# AMC_Connector.net
KiCad netlist of a schematic drawn in Altium Designer
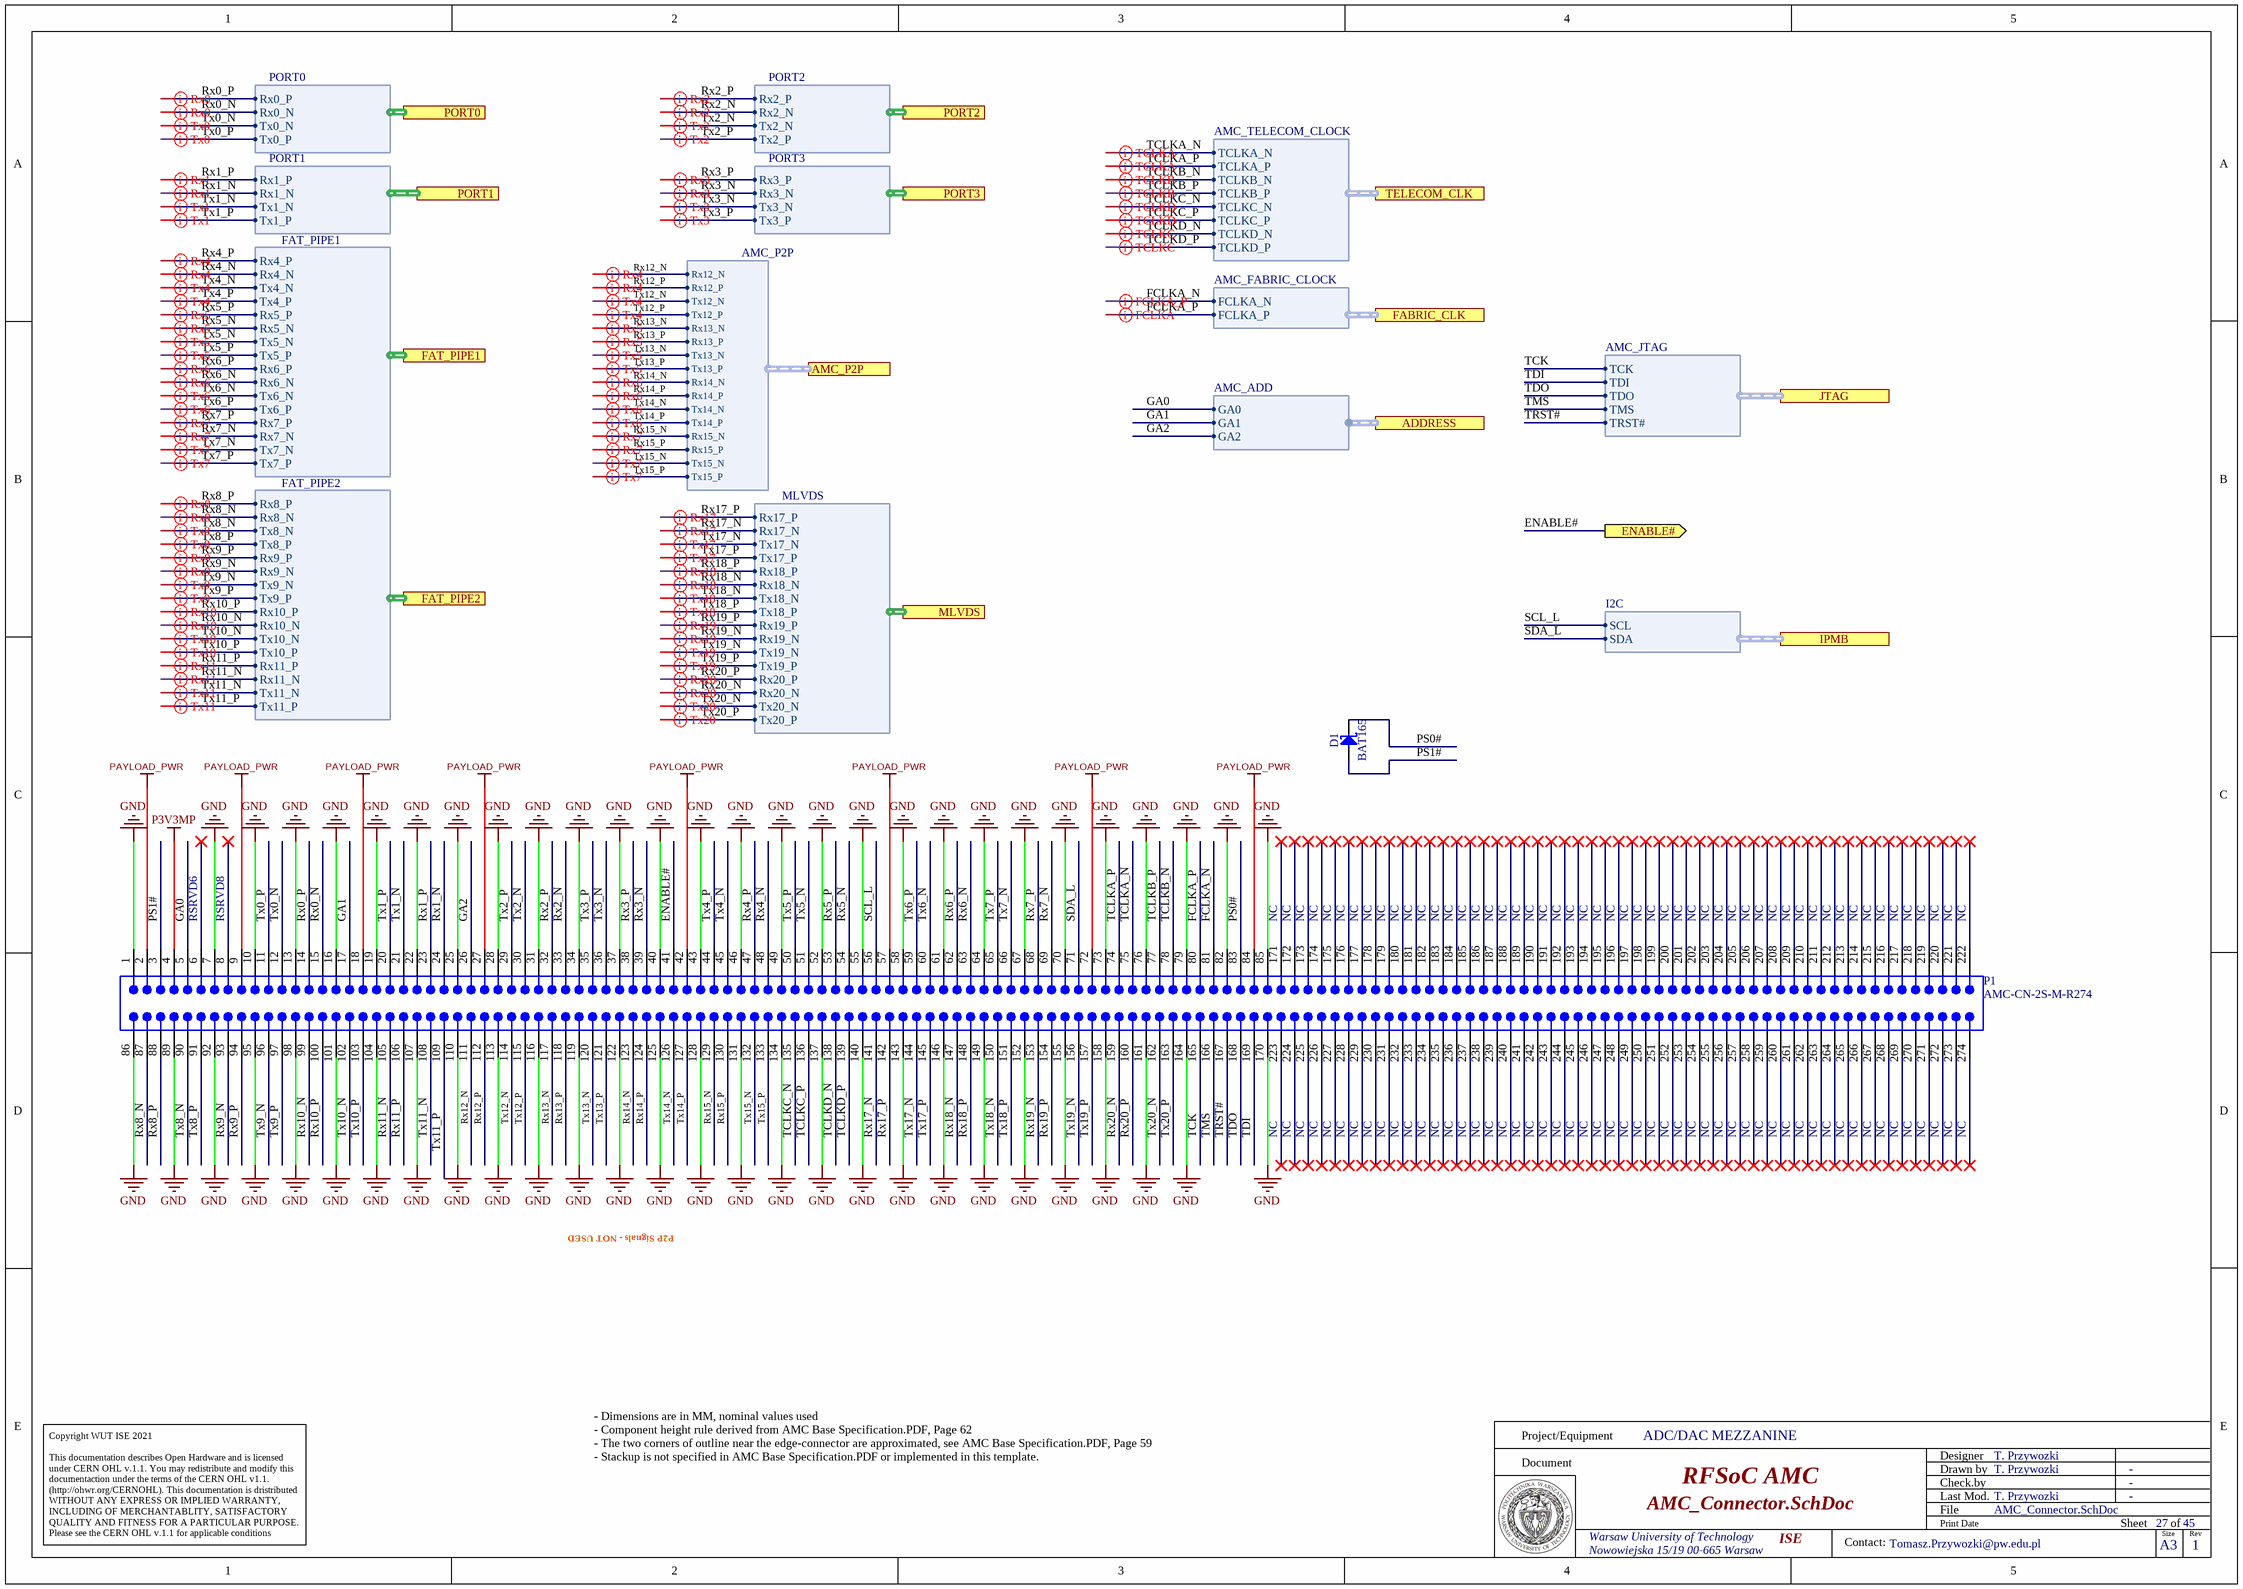
[diagram p0: AMC_Connector.SchDoc]

(export (version "E")
  (design (tool "Eeschema 10.0.6"))
  (components
    (comp (ref "D1")
      (value "BAT165")
      (footprint "SOD2512X110N")
      (description "Schottky Diode")
      (fields
        (field (name "MANUFACTURER") "INFINEON")
        (field (name "VOLTAGE") "40V")
        (field (name "AUTHOR") "CERN DEM JLC")
      )
      (libsource (lib "ICs And Semiconductors") (part "Diode Schottky"))
    )
    (comp (ref "P1")
      (value "AMC-CN-2S-M-R274")
      (footprint "AMC-GF-2D-750-O274")
      (description "Golden finger, AMC, Dual, Opposite, Pitch 0.75mm, 170-Position")
      (fields (field (name "PUBLISHER") "Altium"))
      (libsource (lib "Altium Shanghai") (part "CMP-0001-00058-2"))
    )
  )
  (nets
    (net (code "14") (name "/ENABLE#") (class "Default")
      (node (ref "P1") (pin "41") (pinfunction "41_41") (pintype "passive"))
    )
    (net (code "15") (name "/FCLKA_N") (class "Default")
      (node (ref "P1") (pin "81") (pinfunction "81_81") (pintype "passive"))
    )
    (net (code "16") (name "/FCLKA_P") (class "Default")
      (node (ref "P1") (pin "80") (pinfunction "80_80") (pintype "passive"))
    )
    (net (code "17") (name "/GA0") (class "Default")
      (node (ref "P1") (pin "5") (pinfunction "5_5") (pintype "passive"))
    )
    (net (code "18") (name "/GA1") (class "Default")
      (node (ref "P1") (pin "17") (pinfunction "17_17") (pintype "passive"))
    )
    (net (code "19") (name "/GA2") (class "Default")
      (node (ref "P1") (pin "26") (pinfunction "26_26") (pintype "passive"))
    )
    (net (code "20") (name "/PS0#") (class "Default")
      (node (ref "D1") (pin "1") (pinfunction "C_1") (pintype "passive"))
      (node (ref "P1") (pin "83") (pinfunction "83_83") (pintype "passive"))
    )
    (net (code "21") (name "/PS1#") (class "Default")
      (node (ref "D1") (pin "2") (pinfunction "A_2") (pintype "passive"))
      (node (ref "P1") (pin "3") (pinfunction "3_3") (pintype "passive"))
    )
    (net (code "22") (name "/Rx0_N") (class "Default")
      (node (ref "P1") (pin "15") (pinfunction "15_15") (pintype "passive"))
    )
    (net (code "23") (name "/Rx0_P") (class "Default")
      (node (ref "P1") (pin "14") (pinfunction "14_14") (pintype "passive"))
    )
    (net (code "24") (name "/Rx1_N") (class "Default")
      (node (ref "P1") (pin "24") (pinfunction "24_24") (pintype "passive"))
    )
    (net (code "25") (name "/Rx1_P") (class "Default")
      (node (ref "P1") (pin "23") (pinfunction "23_23") (pintype "passive"))
    )
    (net (code "26") (name "/Rx2_N") (class "Default")
      (node (ref "P1") (pin "33") (pinfunction "33_33") (pintype "passive"))
    )
    (net (code "27") (name "/Rx2_P") (class "Default")
      (node (ref "P1") (pin "32") (pinfunction "32_32") (pintype "passive"))
    )
    (net (code "28") (name "/Rx3_N") (class "Default")
      (node (ref "P1") (pin "39") (pinfunction "39_39") (pintype "passive"))
    )
    (net (code "29") (name "/Rx3_P") (class "Default")
      (node (ref "P1") (pin "38") (pinfunction "38_38") (pintype "passive"))
    )
    (net (code "30") (name "/Rx4_N") (class "Default")
      (node (ref "P1") (pin "48") (pinfunction "48_48") (pintype "passive"))
    )
    (net (code "31") (name "/Rx4_P") (class "Default")
      (node (ref "P1") (pin "47") (pinfunction "47_47") (pintype "passive"))
    )
    (net (code "32") (name "/Rx5_N") (class "Default")
      (node (ref "P1") (pin "54") (pinfunction "54_54") (pintype "passive"))
    )
    (net (code "33") (name "/Rx5_P") (class "Default")
      (node (ref "P1") (pin "53") (pinfunction "53_53") (pintype "passive"))
    )
    (net (code "34") (name "/Rx6_N") (class "Default")
      (node (ref "P1") (pin "63") (pinfunction "63_63") (pintype "passive"))
    )
    (net (code "35") (name "/Rx6_P") (class "Default")
      (node (ref "P1") (pin "62") (pinfunction "62_62") (pintype "passive"))
    )
    (net (code "36") (name "/Rx7_N") (class "Default")
      (node (ref "P1") (pin "69") (pinfunction "69_69") (pintype "passive"))
    )
    (net (code "37") (name "/Rx7_P") (class "Default")
      (node (ref "P1") (pin "68") (pinfunction "68_68") (pintype "passive"))
    )
    (net (code "38") (name "/Rx8_N") (class "Default")
      (node (ref "P1") (pin "87") (pinfunction "87_87") (pintype "passive"))
    )
    (net (code "39") (name "/Rx8_P") (class "Default")
      (node (ref "P1") (pin "88") (pinfunction "88_88") (pintype "passive"))
    )
    (net (code "40") (name "/Rx9_N") (class "Default")
      (node (ref "P1") (pin "93") (pinfunction "93_93") (pintype "passive"))
    )
    (net (code "41") (name "/Rx9_P") (class "Default")
      (node (ref "P1") (pin "94") (pinfunction "94_94") (pintype "passive"))
    )
    (net (code "42") (name "/Rx10_N") (class "Default")
      (node (ref "P1") (pin "99") (pinfunction "99_99") (pintype "passive"))
    )
    (net (code "43") (name "/Rx10_P") (class "Default")
      (node (ref "P1") (pin "100") (pinfunction "100_100") (pintype "passive"))
    )
    (net (code "44") (name "/Rx11_N") (class "Default")
      (node (ref "P1") (pin "105") (pinfunction "105_105") (pintype "passive"))
    )
    (net (code "45") (name "/Rx11_P") (class "Default")
      (node (ref "P1") (pin "106") (pinfunction "106_106") (pintype "passive"))
    )
    (net (code "46") (name "/Rx12_N") (class "Default")
      (node (ref "P1") (pin "111") (pinfunction "111_111") (pintype "passive"))
    )
    (net (code "47") (name "/Rx12_P") (class "Default")
      (node (ref "P1") (pin "112") (pinfunction "112_112") (pintype "passive"))
    )
    (net (code "48") (name "/Rx13_N") (class "Default")
      (node (ref "P1") (pin "117") (pinfunction "117_117") (pintype "passive"))
    )
    (net (code "49") (name "/Rx13_P") (class "Default")
      (node (ref "P1") (pin "118") (pinfunction "118_118") (pintype "passive"))
    )
    (net (code "50") (name "/Rx14_N") (class "Default")
      (node (ref "P1") (pin "123") (pinfunction "123_123") (pintype "passive"))
    )
    (net (code "51") (name "/Rx14_P") (class "Default")
      (node (ref "P1") (pin "124") (pinfunction "124_124") (pintype "passive"))
    )
    (net (code "52") (name "/Rx15_N") (class "Default")
      (node (ref "P1") (pin "129") (pinfunction "129_129") (pintype "passive"))
    )
    (net (code "53") (name "/Rx15_P") (class "Default")
      (node (ref "P1") (pin "130") (pinfunction "130_130") (pintype "passive"))
    )
    (net (code "54") (name "/Rx17_N") (class "Default")
      (node (ref "P1") (pin "141") (pinfunction "141_141") (pintype "passive"))
    )
    (net (code "55") (name "/Rx17_P") (class "Default")
      (node (ref "P1") (pin "142") (pinfunction "142_142") (pintype "passive"))
    )
    (net (code "56") (name "/Rx18_N") (class "Default")
      (node (ref "P1") (pin "147") (pinfunction "147_147") (pintype "passive"))
    )
    (net (code "57") (name "/Rx18_P") (class "Default")
      (node (ref "P1") (pin "148") (pinfunction "148_148") (pintype "passive"))
    )
    (net (code "58") (name "/Rx19_N") (class "Default")
      (node (ref "P1") (pin "153") (pinfunction "153_153") (pintype "passive"))
    )
    (net (code "59") (name "/Rx19_P") (class "Default")
      (node (ref "P1") (pin "154") (pinfunction "154_154") (pintype "passive"))
    )
    (net (code "60") (name "/Rx20_N") (class "Default")
      (node (ref "P1") (pin "159") (pinfunction "159_159") (pintype "passive"))
    )
    (net (code "61") (name "/Rx20_P") (class "Default")
      (node (ref "P1") (pin "160") (pinfunction "160_160") (pintype "passive"))
    )
    (net (code "62") (name "/SCL_L") (class "Default")
      (node (ref "P1") (pin "56") (pinfunction "56_56") (pintype "passive"))
    )
    (net (code "63") (name "/SDA_L") (class "Default")
      (node (ref "P1") (pin "71") (pinfunction "71_71") (pintype "passive"))
    )
    (net (code "64") (name "/TCK") (class "Default")
      (node (ref "P1") (pin "165") (pinfunction "165_165") (pintype "passive"))
    )
    (net (code "65") (name "/TCLKA_N") (class "Default")
      (node (ref "P1") (pin "75") (pinfunction "75_75") (pintype "passive"))
    )
    (net (code "66") (name "/TCLKA_P") (class "Default")
      (node (ref "P1") (pin "74") (pinfunction "74_74") (pintype "passive"))
    )
    (net (code "67") (name "/TCLKB_N") (class "Default")
      (node (ref "P1") (pin "78") (pinfunction "78_78") (pintype "passive"))
    )
    (net (code "68") (name "/TCLKB_P") (class "Default")
      (node (ref "P1") (pin "77") (pinfunction "77_77") (pintype "passive"))
    )
    (net (code "69") (name "/TCLKC_N") (class "Default")
      (node (ref "P1") (pin "135") (pinfunction "135_135") (pintype "passive"))
    )
    (net (code "70") (name "/TCLKC_P") (class "Default")
      (node (ref "P1") (pin "136") (pinfunction "136_136") (pintype "passive"))
    )
    (net (code "71") (name "/TCLKD_N") (class "Default")
      (node (ref "P1") (pin "138") (pinfunction "138_138") (pintype "passive"))
    )
    (net (code "72") (name "/TCLKD_P") (class "Default")
      (node (ref "P1") (pin "139") (pinfunction "139_139") (pintype "passive"))
    )
    (net (code "73") (name "/TDI") (class "Default")
      (node (ref "P1") (pin "169") (pinfunction "169_169") (pintype "passive"))
    )
    (net (code "74") (name "/TDO") (class "Default")
      (node (ref "P1") (pin "168") (pinfunction "168_168") (pintype "passive"))
    )
    (net (code "75") (name "/TMS") (class "Default")
      (node (ref "P1") (pin "166") (pinfunction "166_166") (pintype "passive"))
    )
    (net (code "76") (name "/TRST#") (class "Default")
      (node (ref "P1") (pin "167") (pinfunction "167_167") (pintype "passive"))
    )
    (net (code "77") (name "/Tx0_N") (class "Default")
      (node (ref "P1") (pin "12") (pinfunction "12_12") (pintype "passive"))
    )
    (net (code "78") (name "/Tx0_P") (class "Default")
      (node (ref "P1") (pin "11") (pinfunction "11_11") (pintype "passive"))
    )
    (net (code "79") (name "/Tx1_N") (class "Default")
      (node (ref "P1") (pin "21") (pinfunction "21_21") (pintype "passive"))
    )
    (net (code "80") (name "/Tx1_P") (class "Default")
      (node (ref "P1") (pin "20") (pinfunction "20_20") (pintype "passive"))
    )
    (net (code "81") (name "/Tx2_N") (class "Default")
      (node (ref "P1") (pin "30") (pinfunction "30_30") (pintype "passive"))
    )
    (net (code "82") (name "/Tx2_P") (class "Default")
      (node (ref "P1") (pin "29") (pinfunction "29_29") (pintype "passive"))
    )
    (net (code "83") (name "/Tx3_N") (class "Default")
      (node (ref "P1") (pin "36") (pinfunction "36_36") (pintype "passive"))
    )
    (net (code "84") (name "/Tx3_P") (class "Default")
      (node (ref "P1") (pin "35") (pinfunction "35_35") (pintype "passive"))
    )
    (net (code "85") (name "/Tx4_N") (class "Default")
      (node (ref "P1") (pin "45") (pinfunction "45_45") (pintype "passive"))
    )
    (net (code "86") (name "/Tx4_P") (class "Default")
      (node (ref "P1") (pin "44") (pinfunction "44_44") (pintype "passive"))
    )
    (net (code "87") (name "/Tx5_N") (class "Default")
      (node (ref "P1") (pin "51") (pinfunction "51_51") (pintype "passive"))
    )
    (net (code "88") (name "/Tx5_P") (class "Default")
      (node (ref "P1") (pin "50") (pinfunction "50_50") (pintype "passive"))
    )
    (net (code "89") (name "/Tx6_N") (class "Default")
      (node (ref "P1") (pin "60") (pinfunction "60_60") (pintype "passive"))
    )
    (net (code "90") (name "/Tx6_P") (class "Default")
      (node (ref "P1") (pin "59") (pinfunction "59_59") (pintype "passive"))
    )
    (net (code "91") (name "/Tx7_N") (class "Default")
      (node (ref "P1") (pin "66") (pinfunction "66_66") (pintype "passive"))
    )
    (net (code "92") (name "/Tx7_P") (class "Default")
      (node (ref "P1") (pin "65") (pinfunction "65_65") (pintype "passive"))
    )
    (net (code "93") (name "/Tx8_N") (class "Default")
      (node (ref "P1") (pin "90") (pinfunction "90_90") (pintype "passive"))
    )
    (net (code "94") (name "/Tx8_P") (class "Default")
      (node (ref "P1") (pin "91") (pinfunction "91_91") (pintype "passive"))
    )
    (net (code "95") (name "/Tx9_N") (class "Default")
      (node (ref "P1") (pin "96") (pinfunction "96_96") (pintype "passive"))
    )
    (net (code "96") (name "/Tx9_P") (class "Default")
      (node (ref "P1") (pin "97") (pinfunction "97_97") (pintype "passive"))
    )
    (net (code "97") (name "/Tx10_N") (class "Default")
      (node (ref "P1") (pin "102") (pinfunction "102_102") (pintype "passive"))
    )
    (net (code "98") (name "/Tx10_P") (class "Default")
      (node (ref "P1") (pin "103") (pinfunction "103_103") (pintype "passive"))
    )
    (net (code "99") (name "/Tx11_N") (class "Default")
      (node (ref "P1") (pin "108") (pinfunction "108_108") (pintype "passive"))
    )
    (net (code "100") (name "/Tx11_P") (class "Default")
      (node (ref "P1") (pin "109") (pinfunction "109_109") (pintype "passive"))
    )
    (net (code "101") (name "/Tx12_N") (class "Default")
      (node (ref "P1") (pin "114") (pinfunction "114_114") (pintype "passive"))
    )
    (net (code "102") (name "/Tx12_P") (class "Default")
      (node (ref "P1") (pin "115") (pinfunction "115_115") (pintype "passive"))
    )
    (net (code "103") (name "/Tx13_N") (class "Default")
      (node (ref "P1") (pin "120") (pinfunction "120_120") (pintype "passive"))
    )
    (net (code "104") (name "/Tx13_P") (class "Default")
      (node (ref "P1") (pin "121") (pinfunction "121_121") (pintype "passive"))
    )
    (net (code "105") (name "/Tx14_N") (class "Default")
      (node (ref "P1") (pin "126") (pinfunction "126_126") (pintype "passive"))
    )
    (net (code "106") (name "/Tx14_P") (class "Default")
      (node (ref "P1") (pin "127") (pinfunction "127_127") (pintype "passive"))
    )
    (net (code "107") (name "/Tx15_N") (class "Default")
      (node (ref "P1") (pin "132") (pinfunction "132_132") (pintype "passive"))
    )
    (net (code "108") (name "/Tx15_P") (class "Default")
      (node (ref "P1") (pin "133") (pinfunction "133_133") (pintype "passive"))
    )
    (net (code "109") (name "/Tx17_N") (class "Default")
      (node (ref "P1") (pin "144") (pinfunction "144_144") (pintype "passive"))
    )
    (net (code "110") (name "/Tx17_P") (class "Default")
      (node (ref "P1") (pin "145") (pinfunction "145_145") (pintype "passive"))
    )
    (net (code "111") (name "/Tx18_N") (class "Default")
      (node (ref "P1") (pin "150") (pinfunction "150_150") (pintype "passive"))
    )
    (net (code "112") (name "/Tx18_P") (class "Default")
      (node (ref "P1") (pin "151") (pinfunction "151_151") (pintype "passive"))
    )
    (net (code "113") (name "/Tx19_N") (class "Default")
      (node (ref "P1") (pin "156") (pinfunction "156_156") (pintype "passive"))
    )
    (net (code "114") (name "/Tx19_P") (class "Default")
      (node (ref "P1") (pin "157") (pinfunction "157_157") (pintype "passive"))
    )
    (net (code "115") (name "/Tx20_N") (class "Default")
      (node (ref "P1") (pin "162") (pinfunction "162_162") (pintype "passive"))
    )
    (net (code "116") (name "/Tx20_P") (class "Default")
      (node (ref "P1") (pin "163") (pinfunction "163_163") (pintype "passive"))
    )
    (net (code "130") (name "GND") (class "Default")
      (node (ref "P1") (pin "1") (pinfunction "1_1") (pintype "passive"))
      (node (ref "P1") (pin "10") (pinfunction "10_10") (pintype "passive"))
      (node (ref "P1") (pin "101") (pinfunction "101_101") (pintype "passive"))
      (node (ref "P1") (pin "104") (pinfunction "104_104") (pintype "passive"))
      (node (ref "P1") (pin "107") (pinfunction "107_107") (pintype "passive"))
      (node (ref "P1") (pin "110") (pinfunction "110_110") (pintype "passive"))
      (node (ref "P1") (pin "113") (pinfunction "113_113") (pintype "passive"))
      (node (ref "P1") (pin "116") (pinfunction "116_116") (pintype "passive"))
      (node (ref "P1") (pin "119") (pinfunction "119_119") (pintype "passive"))
      (node (ref "P1") (pin "122") (pinfunction "122_122") (pintype "passive"))
      (node (ref "P1") (pin "125") (pinfunction "125_125") (pintype "passive"))
      (node (ref "P1") (pin "128") (pinfunction "128_128") (pintype "passive"))
      (node (ref "P1") (pin "13") (pinfunction "13_13") (pintype "passive"))
      (node (ref "P1") (pin "131") (pinfunction "131_131") (pintype "passive"))
      (node (ref "P1") (pin "134") (pinfunction "134_134") (pintype "passive"))
      (node (ref "P1") (pin "137") (pinfunction "137_137") (pintype "passive"))
      (node (ref "P1") (pin "140") (pinfunction "140_140") (pintype "passive"))
      (node (ref "P1") (pin "143") (pinfunction "143_143") (pintype "passive"))
      (node (ref "P1") (pin "146") (pinfunction "146_146") (pintype "passive"))
      (node (ref "P1") (pin "149") (pinfunction "149_149") (pintype "passive"))
      (node (ref "P1") (pin "152") (pinfunction "152_152") (pintype "passive"))
      (node (ref "P1") (pin "155") (pinfunction "155_155") (pintype "passive"))
      (node (ref "P1") (pin "158") (pinfunction "158_158") (pintype "passive"))
      (node (ref "P1") (pin "16") (pinfunction "16_16") (pintype "passive"))
      (node (ref "P1") (pin "161") (pinfunction "161_161") (pintype "passive"))
      (node (ref "P1") (pin "164") (pinfunction "164_164") (pintype "passive"))
      (node (ref "P1") (pin "170") (pinfunction "170_170") (pintype "passive"))
      (node (ref "P1") (pin "19") (pinfunction "19_19") (pintype "passive"))
      (node (ref "P1") (pin "22") (pinfunction "22_22") (pintype "passive"))
      (node (ref "P1") (pin "25") (pinfunction "25_25") (pintype "passive"))
      (node (ref "P1") (pin "28") (pinfunction "28_28") (pintype "passive"))
      (node (ref "P1") (pin "31") (pinfunction "31_31") (pintype "passive"))
      (node (ref "P1") (pin "34") (pinfunction "34_34") (pintype "passive"))
      (node (ref "P1") (pin "37") (pinfunction "37_37") (pintype "passive"))
      (node (ref "P1") (pin "40") (pinfunction "40_40") (pintype "passive"))
      (node (ref "P1") (pin "43") (pinfunction "43_43") (pintype "passive"))
      (node (ref "P1") (pin "46") (pinfunction "46_46") (pintype "passive"))
      (node (ref "P1") (pin "49") (pinfunction "49_49") (pintype "passive"))
      (node (ref "P1") (pin "52") (pinfunction "52_52") (pintype "passive"))
      (node (ref "P1") (pin "55") (pinfunction "55_55") (pintype "passive"))
      (node (ref "P1") (pin "58") (pinfunction "58_58") (pintype "passive"))
      (node (ref "P1") (pin "61") (pinfunction "61_61") (pintype "passive"))
      (node (ref "P1") (pin "64") (pinfunction "64_64") (pintype "passive"))
      (node (ref "P1") (pin "67") (pinfunction "67_67") (pintype "passive"))
      (node (ref "P1") (pin "7") (pinfunction "7_7") (pintype "passive"))
      (node (ref "P1") (pin "70") (pinfunction "70_70") (pintype "passive"))
      (node (ref "P1") (pin "73") (pinfunction "73_73") (pintype "passive"))
      (node (ref "P1") (pin "76") (pinfunction "76_76") (pintype "passive"))
      (node (ref "P1") (pin "79") (pinfunction "79_79") (pintype "passive"))
      (node (ref "P1") (pin "82") (pinfunction "82_82") (pintype "passive"))
      (node (ref "P1") (pin "85") (pinfunction "85_85") (pintype "passive"))
      (node (ref "P1") (pin "86") (pinfunction "86_86") (pintype "passive"))
      (node (ref "P1") (pin "89") (pinfunction "89_89") (pintype "passive"))
      (node (ref "P1") (pin "92") (pinfunction "92_92") (pintype "passive"))
      (node (ref "P1") (pin "95") (pinfunction "95_95") (pintype "passive"))
      (node (ref "P1") (pin "98") (pinfunction "98_98") (pintype "passive"))
    )
    (net (code "131") (name "P3V3MP") (class "Default")
      (node (ref "P1") (pin "4") (pinfunction "4_4") (pintype "passive"))
    )
    (net (code "132") (name "PAYLOAD_PWR") (class "Default")
      (node (ref "P1") (pin "18") (pinfunction "18_18") (pintype "passive"))
      (node (ref "P1") (pin "2") (pinfunction "2_2") (pintype "passive"))
      (node (ref "P1") (pin "27") (pinfunction "27_27") (pintype "passive"))
      (node (ref "P1") (pin "42") (pinfunction "42_42") (pintype "passive"))
      (node (ref "P1") (pin "57") (pinfunction "57_57") (pintype "passive"))
      (node (ref "P1") (pin "72") (pinfunction "72_72") (pintype "passive"))
      (node (ref "P1") (pin "84") (pinfunction "84_84") (pintype "passive"))
      (node (ref "P1") (pin "9") (pinfunction "9_9") (pintype "passive"))
    )
    (net (code "133") (name "unconnected-(P1-Pad6)") (class "Default")
      (node (ref "P1") (pin "6") (pinfunction "6_6") (pintype "passive+no_connect"))
    )
    (net (code "134") (name "unconnected-(P1-Pad8)") (class "Default")
      (node (ref "P1") (pin "8") (pinfunction "8_8") (pintype "passive+no_connect"))
    )
    (net (code "135") (name "unconnected-(P1-Pad171)") (class "Default")
      (node (ref "P1") (pin "171") (pinfunction "171_171") (pintype "passive+no_connect"))
    )
    (net (code "136") (name "unconnected-(P1-Pad172)") (class "Default")
      (node (ref "P1") (pin "172") (pinfunction "172_172") (pintype "passive+no_connect"))
    )
    (net (code "137") (name "unconnected-(P1-Pad173)") (class "Default")
      (node (ref "P1") (pin "173") (pinfunction "173_173") (pintype "passive+no_connect"))
    )
    (net (code "138") (name "unconnected-(P1-Pad174)") (class "Default")
      (node (ref "P1") (pin "174") (pinfunction "174_174") (pintype "passive+no_connect"))
    )
    (net (code "139") (name "unconnected-(P1-Pad175)") (class "Default")
      (node (ref "P1") (pin "175") (pinfunction "175_175") (pintype "passive+no_connect"))
    )
    (net (code "140") (name "unconnected-(P1-Pad176)") (class "Default")
      (node (ref "P1") (pin "176") (pinfunction "176_176") (pintype "passive+no_connect"))
    )
    (net (code "141") (name "unconnected-(P1-Pad177)") (class "Default")
      (node (ref "P1") (pin "177") (pinfunction "177_177") (pintype "passive+no_connect"))
    )
    (net (code "142") (name "unconnected-(P1-Pad178)") (class "Default")
      (node (ref "P1") (pin "178") (pinfunction "178_178") (pintype "passive+no_connect"))
    )
    (net (code "143") (name "unconnected-(P1-Pad179)") (class "Default")
      (node (ref "P1") (pin "179") (pinfunction "179_179") (pintype "passive+no_connect"))
    )
    (net (code "144") (name "unconnected-(P1-Pad180)") (class "Default")
      (node (ref "P1") (pin "180") (pinfunction "180_180") (pintype "passive+no_connect"))
    )
    (net (code "145") (name "unconnected-(P1-Pad181)") (class "Default")
      (node (ref "P1") (pin "181") (pinfunction "181_181") (pintype "passive+no_connect"))
    )
    (net (code "146") (name "unconnected-(P1-Pad182)") (class "Default")
      (node (ref "P1") (pin "182") (pinfunction "182_182") (pintype "passive+no_connect"))
    )
    (net (code "147") (name "unconnected-(P1-Pad183)") (class "Default")
      (node (ref "P1") (pin "183") (pinfunction "183_183") (pintype "passive+no_connect"))
    )
    (net (code "148") (name "unconnected-(P1-Pad184)") (class "Default")
      (node (ref "P1") (pin "184") (pinfunction "184_184") (pintype "passive+no_connect"))
    )
    (net (code "149") (name "unconnected-(P1-Pad185)") (class "Default")
      (node (ref "P1") (pin "185") (pinfunction "185_185") (pintype "passive+no_connect"))
    )
    (net (code "150") (name "unconnected-(P1-Pad186)") (class "Default")
      (node (ref "P1") (pin "186") (pinfunction "186_186") (pintype "passive+no_connect"))
    )
    (net (code "151") (name "unconnected-(P1-Pad187)") (class "Default")
      (node (ref "P1") (pin "187") (pinfunction "187_187") (pintype "passive+no_connect"))
    )
    (net (code "152") (name "unconnected-(P1-Pad188)") (class "Default")
      (node (ref "P1") (pin "188") (pinfunction "188_188") (pintype "passive+no_connect"))
    )
    (net (code "153") (name "unconnected-(P1-Pad189)") (class "Default")
      (node (ref "P1") (pin "189") (pinfunction "189_189") (pintype "passive+no_connect"))
    )
    (net (code "154") (name "unconnected-(P1-Pad190)") (class "Default")
      (node (ref "P1") (pin "190") (pinfunction "190_190") (pintype "passive+no_connect"))
    )
    (net (code "155") (name "unconnected-(P1-Pad191)") (class "Default")
      (node (ref "P1") (pin "191") (pinfunction "191_191") (pintype "passive+no_connect"))
    )
    (net (code "156") (name "unconnected-(P1-Pad192)") (class "Default")
      (node (ref "P1") (pin "192") (pinfunction "192_192") (pintype "passive+no_connect"))
    )
    (net (code "157") (name "unconnected-(P1-Pad193)") (class "Default")
      (node (ref "P1") (pin "193") (pinfunction "193_193") (pintype "passive+no_connect"))
    )
    (net (code "158") (name "unconnected-(P1-Pad194)") (class "Default")
      (node (ref "P1") (pin "194") (pinfunction "194_194") (pintype "passive+no_connect"))
    )
    (net (code "159") (name "unconnected-(P1-Pad195)") (class "Default")
      (node (ref "P1") (pin "195") (pinfunction "195_195") (pintype "passive+no_connect"))
    )
    (net (code "160") (name "unconnected-(P1-Pad196)") (class "Default")
      (node (ref "P1") (pin "196") (pinfunction "196_196") (pintype "passive+no_connect"))
    )
    (net (code "161") (name "unconnected-(P1-Pad197)") (class "Default")
      (node (ref "P1") (pin "197") (pinfunction "197_197") (pintype "passive+no_connect"))
    )
    (net (code "162") (name "unconnected-(P1-Pad198)") (class "Default")
      (node (ref "P1") (pin "198") (pinfunction "198_198") (pintype "passive+no_connect"))
    )
    (net (code "163") (name "unconnected-(P1-Pad199)") (class "Default")
      (node (ref "P1") (pin "199") (pinfunction "199_199") (pintype "passive+no_connect"))
    )
    (net (code "164") (name "unconnected-(P1-Pad200)") (class "Default")
      (node (ref "P1") (pin "200") (pinfunction "200_200") (pintype "passive+no_connect"))
    )
    (net (code "165") (name "unconnected-(P1-Pad201)") (class "Default")
      (node (ref "P1") (pin "201") (pinfunction "201_201") (pintype "passive+no_connect"))
    )
    (net (code "166") (name "unconnected-(P1-Pad202)") (class "Default")
      (node (ref "P1") (pin "202") (pinfunction "202_202") (pintype "passive+no_connect"))
    )
    (net (code "167") (name "unconnected-(P1-Pad203)") (class "Default")
      (node (ref "P1") (pin "203") (pinfunction "203_203") (pintype "passive+no_connect"))
    )
    (net (code "168") (name "unconnected-(P1-Pad204)") (class "Default")
      (node (ref "P1") (pin "204") (pinfunction "204_204") (pintype "passive+no_connect"))
    )
    (net (code "169") (name "unconnected-(P1-Pad205)") (class "Default")
      (node (ref "P1") (pin "205") (pinfunction "205_205") (pintype "passive+no_connect"))
    )
    (net (code "170") (name "unconnected-(P1-Pad206)") (class "Default")
      (node (ref "P1") (pin "206") (pinfunction "206_206") (pintype "passive+no_connect"))
    )
    (net (code "171") (name "unconnected-(P1-Pad207)") (class "Default")
      (node (ref "P1") (pin "207") (pinfunction "207_207") (pintype "passive+no_connect"))
    )
    (net (code "172") (name "unconnected-(P1-Pad208)") (class "Default")
      (node (ref "P1") (pin "208") (pinfunction "208_208") (pintype "passive+no_connect"))
    )
    (net (code "173") (name "unconnected-(P1-Pad209)") (class "Default")
      (node (ref "P1") (pin "209") (pinfunction "209_209") (pintype "passive+no_connect"))
    )
    (net (code "174") (name "unconnected-(P1-Pad210)") (class "Default")
      (node (ref "P1") (pin "210") (pinfunction "210_210") (pintype "passive+no_connect"))
    )
    (net (code "175") (name "unconnected-(P1-Pad211)") (class "Default")
      (node (ref "P1") (pin "211") (pinfunction "211_211") (pintype "passive+no_connect"))
    )
    (net (code "176") (name "unconnected-(P1-Pad212)") (class "Default")
      (node (ref "P1") (pin "212") (pinfunction "212_212") (pintype "passive+no_connect"))
    )
    (net (code "177") (name "unconnected-(P1-Pad213)") (class "Default")
      (node (ref "P1") (pin "213") (pinfunction "213_213") (pintype "passive+no_connect"))
    )
    (net (code "178") (name "unconnected-(P1-Pad214)") (class "Default")
      (node (ref "P1") (pin "214") (pinfunction "214_214") (pintype "passive+no_connect"))
    )
    (net (code "179") (name "unconnected-(P1-Pad215)") (class "Default")
      (node (ref "P1") (pin "215") (pinfunction "215_215") (pintype "passive+no_connect"))
    )
    (net (code "180") (name "unconnected-(P1-Pad216)") (class "Default")
      (node (ref "P1") (pin "216") (pinfunction "216_216") (pintype "passive+no_connect"))
    )
    (net (code "181") (name "unconnected-(P1-Pad217)") (class "Default")
      (node (ref "P1") (pin "217") (pinfunction "217_217") (pintype "passive+no_connect"))
    )
    (net (code "182") (name "unconnected-(P1-Pad218)") (class "Default")
      (node (ref "P1") (pin "218") (pinfunction "218_218") (pintype "passive+no_connect"))
    )
    (net (code "183") (name "unconnected-(P1-Pad219)") (class "Default")
      (node (ref "P1") (pin "219") (pinfunction "219_219") (pintype "passive+no_connect"))
    )
    (net (code "184") (name "unconnected-(P1-Pad220)") (class "Default")
      (node (ref "P1") (pin "220") (pinfunction "220_220") (pintype "passive+no_connect"))
    )
    (net (code "185") (name "unconnected-(P1-Pad221)") (class "Default")
      (node (ref "P1") (pin "221") (pinfunction "221_221") (pintype "passive+no_connect"))
    )
    (net (code "186") (name "unconnected-(P1-Pad222)") (class "Default")
      (node (ref "P1") (pin "222") (pinfunction "222_222") (pintype "passive+no_connect"))
    )
    (net (code "187") (name "unconnected-(P1-Pad223)") (class "Default")
      (node (ref "P1") (pin "223") (pinfunction "223_223") (pintype "passive+no_connect"))
    )
    (net (code "188") (name "unconnected-(P1-Pad224)") (class "Default")
      (node (ref "P1") (pin "224") (pinfunction "224_224") (pintype "passive+no_connect"))
    )
    (net (code "189") (name "unconnected-(P1-Pad225)") (class "Default")
      (node (ref "P1") (pin "225") (pinfunction "225_225") (pintype "passive+no_connect"))
    )
    (net (code "190") (name "unconnected-(P1-Pad226)") (class "Default")
      (node (ref "P1") (pin "226") (pinfunction "226_226") (pintype "passive+no_connect"))
    )
    (net (code "191") (name "unconnected-(P1-Pad227)") (class "Default")
      (node (ref "P1") (pin "227") (pinfunction "227_227") (pintype "passive+no_connect"))
    )
    (net (code "192") (name "unconnected-(P1-Pad228)") (class "Default")
      (node (ref "P1") (pin "228") (pinfunction "228_228") (pintype "passive+no_connect"))
    )
    (net (code "193") (name "unconnected-(P1-Pad229)") (class "Default")
      (node (ref "P1") (pin "229") (pinfunction "229_229") (pintype "passive+no_connect"))
    )
    (net (code "194") (name "unconnected-(P1-Pad230)") (class "Default")
      (node (ref "P1") (pin "230") (pinfunction "230_230") (pintype "passive+no_connect"))
    )
    (net (code "195") (name "unconnected-(P1-Pad231)") (class "Default")
      (node (ref "P1") (pin "231") (pinfunction "231_231") (pintype "passive+no_connect"))
    )
    (net (code "196") (name "unconnected-(P1-Pad232)") (class "Default")
      (node (ref "P1") (pin "232") (pinfunction "232_232") (pintype "passive+no_connect"))
    )
    (net (code "197") (name "unconnected-(P1-Pad233)") (class "Default")
      (node (ref "P1") (pin "233") (pinfunction "233_233") (pintype "passive+no_connect"))
    )
    (net (code "198") (name "unconnected-(P1-Pad234)") (class "Default")
      (node (ref "P1") (pin "234") (pinfunction "234_234") (pintype "passive+no_connect"))
    )
    (net (code "199") (name "unconnected-(P1-Pad235)") (class "Default")
      (node (ref "P1") (pin "235") (pinfunction "235_235") (pintype "passive+no_connect"))
    )
    (net (code "200") (name "unconnected-(P1-Pad236)") (class "Default")
      (node (ref "P1") (pin "236") (pinfunction "236_236") (pintype "passive+no_connect"))
    )
    (net (code "201") (name "unconnected-(P1-Pad237)") (class "Default")
      (node (ref "P1") (pin "237") (pinfunction "237_237") (pintype "passive+no_connect"))
    )
    (net (code "202") (name "unconnected-(P1-Pad238)") (class "Default")
      (node (ref "P1") (pin "238") (pinfunction "238_238") (pintype "passive+no_connect"))
    )
    (net (code "203") (name "unconnected-(P1-Pad239)") (class "Default")
      (node (ref "P1") (pin "239") (pinfunction "239_239") (pintype "passive+no_connect"))
    )
    (net (code "204") (name "unconnected-(P1-Pad240)") (class "Default")
      (node (ref "P1") (pin "240") (pinfunction "240_240") (pintype "passive+no_connect"))
    )
    (net (code "205") (name "unconnected-(P1-Pad241)") (class "Default")
      (node (ref "P1") (pin "241") (pinfunction "241_241") (pintype "passive+no_connect"))
    )
    (net (code "206") (name "unconnected-(P1-Pad242)") (class "Default")
      (node (ref "P1") (pin "242") (pinfunction "242_242") (pintype "passive+no_connect"))
    )
    (net (code "207") (name "unconnected-(P1-Pad243)") (class "Default")
      (node (ref "P1") (pin "243") (pinfunction "243_243") (pintype "passive+no_connect"))
    )
    (net (code "208") (name "unconnected-(P1-Pad244)") (class "Default")
      (node (ref "P1") (pin "244") (pinfunction "244_244") (pintype "passive+no_connect"))
    )
    (net (code "209") (name "unconnected-(P1-Pad245)") (class "Default")
      (node (ref "P1") (pin "245") (pinfunction "245_245") (pintype "passive+no_connect"))
    )
    (net (code "210") (name "unconnected-(P1-Pad246)") (class "Default")
      (node (ref "P1") (pin "246") (pinfunction "246_246") (pintype "passive+no_connect"))
    )
    (net (code "211") (name "unconnected-(P1-Pad247)") (class "Default")
      (node (ref "P1") (pin "247") (pinfunction "247_247") (pintype "passive+no_connect"))
    )
    (net (code "212") (name "unconnected-(P1-Pad248)") (class "Default")
      (node (ref "P1") (pin "248") (pinfunction "248_248") (pintype "passive+no_connect"))
    )
    (net (code "213") (name "unconnected-(P1-Pad249)") (class "Default")
      (node (ref "P1") (pin "249") (pinfunction "249_249") (pintype "passive+no_connect"))
    )
    (net (code "214") (name "unconnected-(P1-Pad250)") (class "Default")
      (node (ref "P1") (pin "250") (pinfunction "250_250") (pintype "passive+no_connect"))
    )
    (net (code "215") (name "unconnected-(P1-Pad251)") (class "Default")
      (node (ref "P1") (pin "251") (pinfunction "251_251") (pintype "passive+no_connect"))
    )
    (net (code "216") (name "unconnected-(P1-Pad252)") (class "Default")
      (node (ref "P1") (pin "252") (pinfunction "252_252") (pintype "passive+no_connect"))
    )
    (net (code "217") (name "unconnected-(P1-Pad253)") (class "Default")
      (node (ref "P1") (pin "253") (pinfunction "253_253") (pintype "passive+no_connect"))
    )
    (net (code "218") (name "unconnected-(P1-Pad254)") (class "Default")
      (node (ref "P1") (pin "254") (pinfunction "254_254") (pintype "passive+no_connect"))
    )
    (net (code "219") (name "unconnected-(P1-Pad255)") (class "Default")
      (node (ref "P1") (pin "255") (pinfunction "255_255") (pintype "passive+no_connect"))
    )
    (net (code "220") (name "unconnected-(P1-Pad256)") (class "Default")
      (node (ref "P1") (pin "256") (pinfunction "256_256") (pintype "passive+no_connect"))
    )
    (net (code "221") (name "unconnected-(P1-Pad257)") (class "Default")
      (node (ref "P1") (pin "257") (pinfunction "257_257") (pintype "passive+no_connect"))
    )
    (net (code "222") (name "unconnected-(P1-Pad258)") (class "Default")
      (node (ref "P1") (pin "258") (pinfunction "258_258") (pintype "passive+no_connect"))
    )
    (net (code "223") (name "unconnected-(P1-Pad259)") (class "Default")
      (node (ref "P1") (pin "259") (pinfunction "259_259") (pintype "passive+no_connect"))
    )
    (net (code "224") (name "unconnected-(P1-Pad260)") (class "Default")
      (node (ref "P1") (pin "260") (pinfunction "260_260") (pintype "passive+no_connect"))
    )
    (net (code "225") (name "unconnected-(P1-Pad261)") (class "Default")
      (node (ref "P1") (pin "261") (pinfunction "261_261") (pintype "passive+no_connect"))
    )
    (net (code "226") (name "unconnected-(P1-Pad262)") (class "Default")
      (node (ref "P1") (pin "262") (pinfunction "262_262") (pintype "passive+no_connect"))
    )
    (net (code "227") (name "unconnected-(P1-Pad263)") (class "Default")
      (node (ref "P1") (pin "263") (pinfunction "263_263") (pintype "passive+no_connect"))
    )
    (net (code "228") (name "unconnected-(P1-Pad264)") (class "Default")
      (node (ref "P1") (pin "264") (pinfunction "264_264") (pintype "passive+no_connect"))
    )
    (net (code "229") (name "unconnected-(P1-Pad265)") (class "Default")
      (node (ref "P1") (pin "265") (pinfunction "265_265") (pintype "passive+no_connect"))
    )
    (net (code "230") (name "unconnected-(P1-Pad266)") (class "Default")
      (node (ref "P1") (pin "266") (pinfunction "266_266") (pintype "passive+no_connect"))
    )
    (net (code "231") (name "unconnected-(P1-Pad267)") (class "Default")
      (node (ref "P1") (pin "267") (pinfunction "267_267") (pintype "passive+no_connect"))
    )
    (net (code "232") (name "unconnected-(P1-Pad268)") (class "Default")
      (node (ref "P1") (pin "268") (pinfunction "268_268") (pintype "passive+no_connect"))
    )
    (net (code "233") (name "unconnected-(P1-Pad269)") (class "Default")
      (node (ref "P1") (pin "269") (pinfunction "269_269") (pintype "passive+no_connect"))
    )
    (net (code "234") (name "unconnected-(P1-Pad270)") (class "Default")
      (node (ref "P1") (pin "270") (pinfunction "270_270") (pintype "passive+no_connect"))
    )
    (net (code "235") (name "unconnected-(P1-Pad271)") (class "Default")
      (node (ref "P1") (pin "271") (pinfunction "271_271") (pintype "passive+no_connect"))
    )
    (net (code "236") (name "unconnected-(P1-Pad272)") (class "Default")
      (node (ref "P1") (pin "272") (pinfunction "272_272") (pintype "passive+no_connect"))
    )
    (net (code "237") (name "unconnected-(P1-Pad273)") (class "Default")
      (node (ref "P1") (pin "273") (pinfunction "273_273") (pintype "passive+no_connect"))
    )
    (net (code "238") (name "unconnected-(P1-Pad274)") (class "Default")
      (node (ref "P1") (pin "274") (pinfunction "274_274") (pintype "passive+no_connect"))
    )
  )
)
